# PSU.net
KiCad netlist of a schematic drawn in Altium Designer
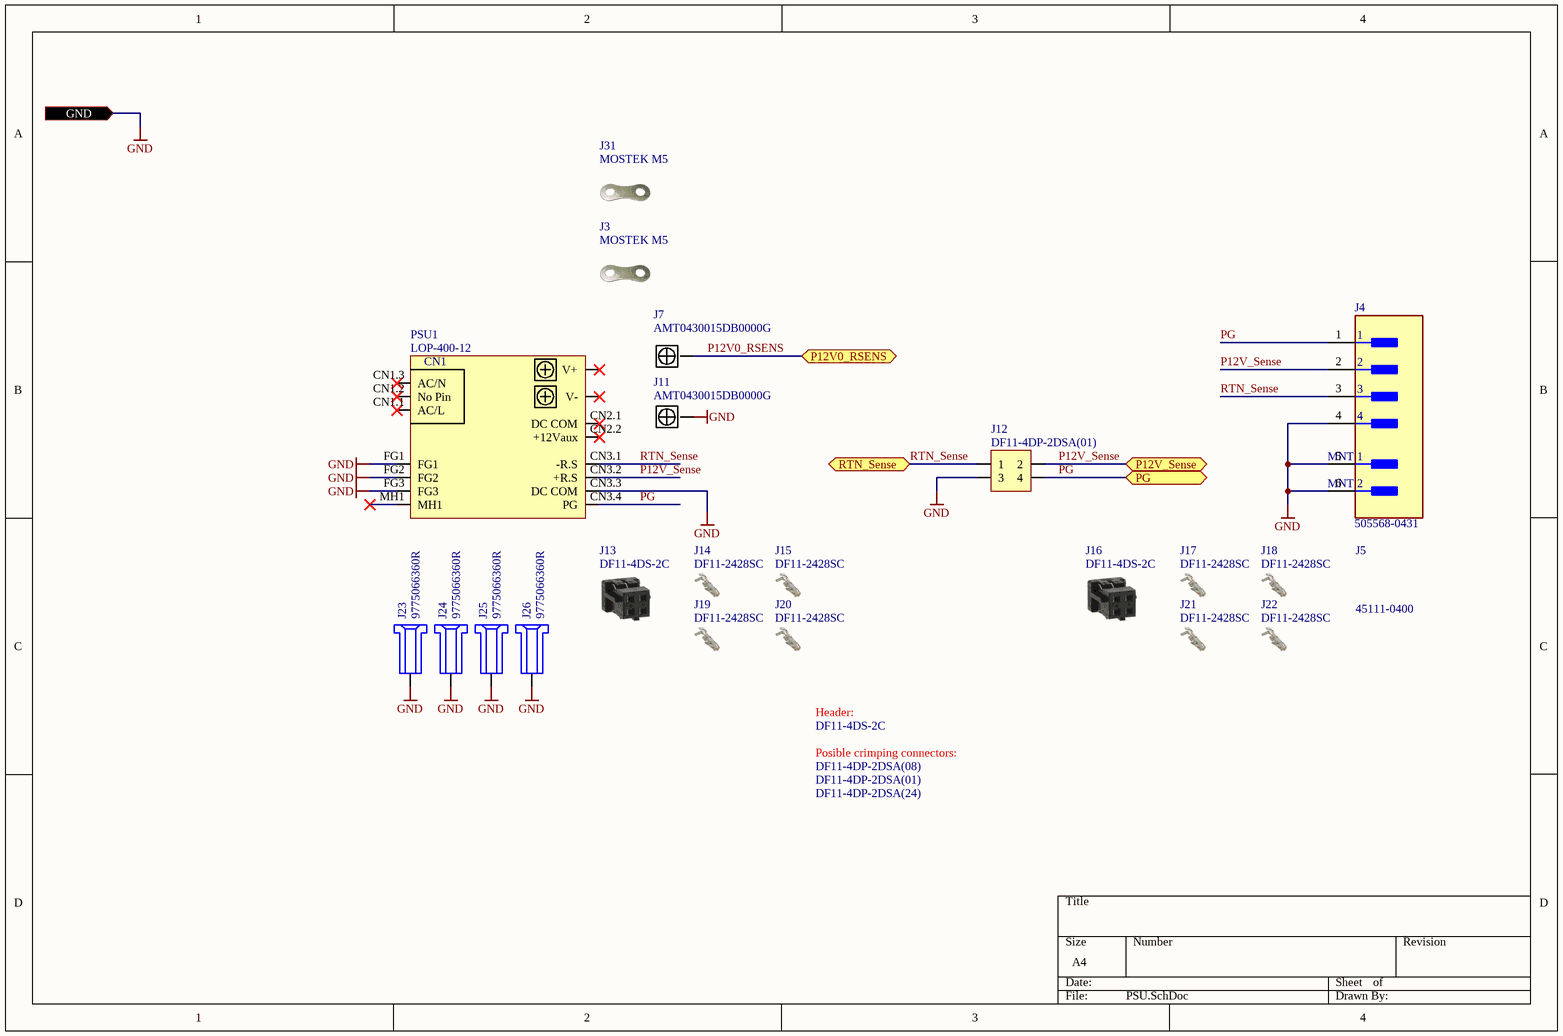
[diagram p0: PSU.SchDoc]

(export (version "E")
  (design (tool "Eeschema 10.0.6"))
  (components
    (comp (ref "J3")
      (value "MOSTEK M5")
      (description "Mostek do tabliczki zaciskowej M5")
      (fields (field (name "AUTHOR") "LPA"))
      (libsource (lib "DIOT_PSU") (part "Mostek M5"))
    )
    (comp (ref "J4")
      (value "505568-0431")
      (footprint "FP-505568-0431-MFG")
      (description "Connector Wire to Board Micro-Lock Plug 4 Position 1.25mm Straight Surface Mount Black")
      (libsource (lib "TechnoSystem Workspace") (part "3b6f738a5616415d78381ad43816e4a"))
    )
    (comp (ref "J5")
      (value "45111-0400")
      (footprint "45111-0400")
      (description "Molex 45111-0400 Rectangular Cable Assemblies Micro-Lock Plus 04P Ots Assembly,")
      (libsource (lib "TechnoSystem Workspace") (part "45111-0400"))
    )
    (comp (ref "J7")
      (value "AMT0430015DB0000G")
      (footprint "AMT0430015DB0000G")
      (description "4 Pin Screw Terminal, Power Tap M3 Through Hole")
      (fields (field (name "MANUFACTURER") "Amphenol Anytek") (field (name "AUTHOR") "LPA"))
      (libsource (lib "EDA-04213-V3-0_project") (part "AMT0430015DB0000G"))
    )
    (comp (ref "J11")
      (value "AMT0430015DB0000G")
      (footprint "AMT0430015DB0000G")
      (description "4 Pin Screw Terminal, Power Tap M3 Through Hole")
      (fields (field (name "MANUFACTURER") "Amphenol Anytek") (field (name "AUTHOR") "LPA"))
      (libsource (lib "EDA-04213-V3-0_project") (part "AMT0430015DB0000G"))
    )
    (comp (ref "J12")
      (value "DF11-4DP-2DSA(01)")
      (footprint "DF11-4DP-2DSA(01)")
      (fields (field (name "MANUFACTURER") "Hirose Electric Co Ltd") (field (name "AUTHOR") "LPA"))
      (libsource (lib "EDA-04213-V3-0_project") (part "DF11-4DP-2DSA(01)"))
    )
    (comp (ref "J13")
      (value "DF11-4DS-2C")
      (footprint "DF11-4DS-2C")
      (description "4 Rectangular Connectors - Housings Receptacle Black 0.079\" (2.00mm)")
      (fields (field (name "MANUFACTURER") "Hirose Electric Co Ltd") (field (name "AUTHOR") "LPA"))
      (libsource (lib "EDA-04213-V3-0_project") (part "DF11-4DS-2C"))
    )
    (comp (ref "J14")
      (value "DF11-2428SC")
      (description "Socket Contact Tin 24-28 AWG Crimp")
      (fields (field (name "MANUFACTURER") "Hirose Electric Co Ltd") (field (name "AUTHOR") "LPA"))
      (libsource (lib "DIOT_PSU_integrated") (part "DF11-2428SC"))
    )
    (comp (ref "J15")
      (value "DF11-2428SC")
      (description "Socket Contact Tin 24-28 AWG Crimp")
      (fields (field (name "MANUFACTURER") "Hirose Electric Co Ltd") (field (name "AUTHOR") "LPA"))
      (libsource (lib "DIOT_PSU_integrated") (part "DF11-2428SC"))
    )
    (comp (ref "J16")
      (value "DF11-4DS-2C")
      (footprint "DF11-4DS-2C")
      (description "4 Rectangular Connectors - Housings Receptacle Black 0.079\" (2.00mm)")
      (fields (field (name "MANUFACTURER") "Hirose Electric Co Ltd") (field (name "AUTHOR") "LPA"))
      (libsource (lib "EDA-04213-V3-0_project") (part "DF11-4DS-2C"))
    )
    (comp (ref "J17")
      (value "DF11-2428SC")
      (description "Socket Contact Tin 24-28 AWG Crimp")
      (fields (field (name "MANUFACTURER") "Hirose Electric Co Ltd") (field (name "AUTHOR") "LPA"))
      (libsource (lib "DIOT_PSU_integrated") (part "DF11-2428SC"))
    )
    (comp (ref "J18")
      (value "DF11-2428SC")
      (description "Socket Contact Tin 24-28 AWG Crimp")
      (fields (field (name "MANUFACTURER") "Hirose Electric Co Ltd") (field (name "AUTHOR") "LPA"))
      (libsource (lib "DIOT_PSU_integrated") (part "DF11-2428SC"))
    )
    (comp (ref "J19")
      (value "DF11-2428SC")
      (description "Socket Contact Tin 24-28 AWG Crimp")
      (fields (field (name "MANUFACTURER") "Hirose Electric Co Ltd") (field (name "AUTHOR") "LPA"))
      (libsource (lib "DIOT_PSU_integrated") (part "DF11-2428SC"))
    )
    (comp (ref "J20")
      (value "DF11-2428SC")
      (description "Socket Contact Tin 24-28 AWG Crimp")
      (fields (field (name "MANUFACTURER") "Hirose Electric Co Ltd") (field (name "AUTHOR") "LPA"))
      (libsource (lib "DIOT_PSU_integrated") (part "DF11-2428SC"))
    )
    (comp (ref "J21")
      (value "DF11-2428SC")
      (description "Socket Contact Tin 24-28 AWG Crimp")
      (fields (field (name "MANUFACTURER") "Hirose Electric Co Ltd") (field (name "AUTHOR") "LPA"))
      (libsource (lib "DIOT_PSU_integrated") (part "DF11-2428SC"))
    )
    (comp (ref "J22")
      (value "DF11-2428SC")
      (description "Socket Contact Tin 24-28 AWG Crimp")
      (fields (field (name "MANUFACTURER") "Hirose Electric Co Ltd") (field (name "AUTHOR") "LPA"))
      (libsource (lib "DIOT_PSU_integrated") (part "DF11-2428SC"))
    )
    (comp (ref "J23")
      (value "9775066360R")
      (footprint "9775066360R")
      (description "Round Standoff Threaded M3 Steel 0.039\" (1.00mm)")
      (fields (field (name "MANUFACTURER") "Würth Elektronik") (field (name "AUTHOR") "LPA"))
      (libsource (lib "EDA-04213-V3-0_project") (part "9775066360R"))
    )
    (comp (ref "J24")
      (value "9775066360R")
      (footprint "9775066360R")
      (description "Round Standoff Threaded M3 Steel 0.039\" (1.00mm)")
      (fields (field (name "MANUFACTURER") "Würth Elektronik") (field (name "AUTHOR") "LPA"))
      (libsource (lib "EDA-04213-V3-0_project") (part "9775066360R"))
    )
    (comp (ref "J25")
      (value "9775066360R")
      (footprint "9775066360R")
      (description "Round Standoff Threaded M3 Steel 0.039\" (1.00mm)")
      (fields (field (name "MANUFACTURER") "Würth Elektronik") (field (name "AUTHOR") "LPA"))
      (libsource (lib "EDA-04213-V3-0_project") (part "9775066360R"))
    )
    (comp (ref "J26")
      (value "9775066360R")
      (footprint "9775066360R")
      (description "Round Standoff Threaded M3 Steel 0.039\" (1.00mm)")
      (fields (field (name "MANUFACTURER") "Würth Elektronik") (field (name "AUTHOR") "LPA"))
      (libsource (lib "EDA-04213-V3-0_project") (part "9775066360R"))
    )
    (comp (ref "J31")
      (value "MOSTEK M5")
      (description "Mostek do tabliczki zaciskowej M5")
      (fields (field (name "AUTHOR") "LPA"))
      (libsource (lib "DIOT_PSU") (part "Mostek M5"))
    )
    (comp (ref "PSU1")
      (value "LOP-400")
      (footprint "LOP-400-12")
      (fields
        (field (name "PART NUMBER") "LOP-400-12")
        (field (name "MANUFACTURER") "MEANWELL")
        (field (name "MANUFACTURER PART NUMBER") "LOP-400-12")
        (field (name "AUTHOR") "LPA")
      )
      (libsource (lib "EDA-04213-V3-0_project") (part "LOP-400-12"))
    )
  )
  (nets
    (net (code "1") (name "/P12V0_RSENS") (class "Default")
      (node (ref "J7") (pin "1") (pinfunction "1_1") (pintype "passive"))
    )
    (net (code "2") (name "/P12V_Sense") (class "Default")
      (node (ref "J12") (pin "2") (pinfunction "2_2") (pintype "passive"))
      (node (ref "J4") (pin "2") (pinfunction "2_2") (pintype "passive"))
      (node (ref "PSU1") (pin "CN3.2") (pinfunction "+R.S_CN3.2") (pintype "passive"))
    )
    (net (code "3") (name "/PG") (class "Default")
      (node (ref "J12") (pin "4") (pinfunction "4_4") (pintype "passive"))
      (node (ref "J4") (pin "1") (pinfunction "1_1") (pintype "passive"))
      (node (ref "PSU1") (pin "CN3.4") (pinfunction "PG_CN3.4") (pintype "passive"))
    )
    (net (code "4") (name "/RTN_Sense") (class "Default")
      (node (ref "J12") (pin "1") (pinfunction "1_1") (pintype "passive"))
      (node (ref "J4") (pin "3") (pinfunction "3_3") (pintype "passive"))
      (node (ref "PSU1") (pin "CN3.1") (pinfunction "-R.S_CN3.1") (pintype "passive"))
    )
    (net (code "5") (name "GND") (class "Default")
      (node (ref "J11") (pin "1") (pinfunction "1_1") (pintype "passive"))
      (node (ref "J12") (pin "3") (pinfunction "3_3") (pintype "passive"))
      (node (ref "J23") (pin "1") (pinfunction "1_1") (pintype "passive"))
      (node (ref "J24") (pin "1") (pinfunction "1_1") (pintype "passive"))
      (node (ref "J25") (pin "1") (pinfunction "1_1") (pintype "passive"))
      (node (ref "J26") (pin "1") (pinfunction "1_1") (pintype "passive"))
      (node (ref "J4") (pin "4") (pinfunction "4_4") (pintype "passive"))
      (node (ref "J4") (pin "5") (pinfunction "MNT_1_5") (pintype "passive"))
      (node (ref "J4") (pin "6") (pinfunction "MNT_2_6") (pintype "passive"))
      (node (ref "PSU1") (pin "CN3.3") (pinfunction "DC_COM_CN3.3") (pintype "passive"))
      (node (ref "PSU1") (pin "FG1") (pinfunction "FG1_FG1") (pintype "passive"))
      (node (ref "PSU1") (pin "FG2") (pinfunction "FG2_FG2") (pintype "passive"))
      (node (ref "PSU1") (pin "FG3") (pinfunction "FG3_FG3") (pintype "passive"))
    )
    (net (code "6") (name "unconnected-(PSU1-+12Vaux-PadCN2.2)") (class "Default")
      (node (ref "PSU1") (pin "CN2.2") (pinfunction "+12Vaux_CN2.2") (pintype "passive+no_connect"))
    )
    (net (code "7") (name "unconnected-(PSU1-AC{slash}L-PadCN1.1)") (class "Default")
      (node (ref "PSU1") (pin "CN1.1") (pinfunction "AC/L_CN1.1") (pintype "passive+no_connect"))
    )
    (net (code "8") (name "unconnected-(PSU1-AC{slash}N-PadCN1.3)") (class "Default")
      (node (ref "PSU1") (pin "CN1.3") (pinfunction "AC/N_CN1.3") (pintype "passive+no_connect"))
    )
    (net (code "9") (name "unconnected-(PSU1-DC_COM-PadCN2.1)") (class "Default")
      (node (ref "PSU1") (pin "CN2.1") (pinfunction "DC_COM_CN2.1") (pintype "passive+no_connect"))
    )
    (net (code "10") (name "unconnected-(PSU1-No_Pin-PadCN1.2)") (class "Default")
      (node (ref "PSU1") (pin "CN1.2") (pinfunction "No_Pin_CN1.2") (pintype "passive+no_connect"))
    )
    (net (code "11") (name "unconnected-(PSU1-PadMH1)") (class "Default")
      (node (ref "PSU1") (pin "MH1") (pinfunction "MH1_MH1") (pintype "passive+no_connect"))
    )
    (net (code "12") (name "unconnected-(PSU1-PadV+)") (class "Default")
      (node (ref "PSU1") (pin "V+") (pinfunction "V+_V+") (pintype "passive+no_connect"))
    )
    (net (code "13") (name "unconnected-(PSU1-PadV-)") (class "Default")
      (node (ref "PSU1") (pin "V-") (pinfunction "V-_V-") (pintype "passive+no_connect"))
    )
  )
)
